# 14_RAM-DDR3_1X16BIT.net
KiCad netlist of a schematic drawn in Altium Designer
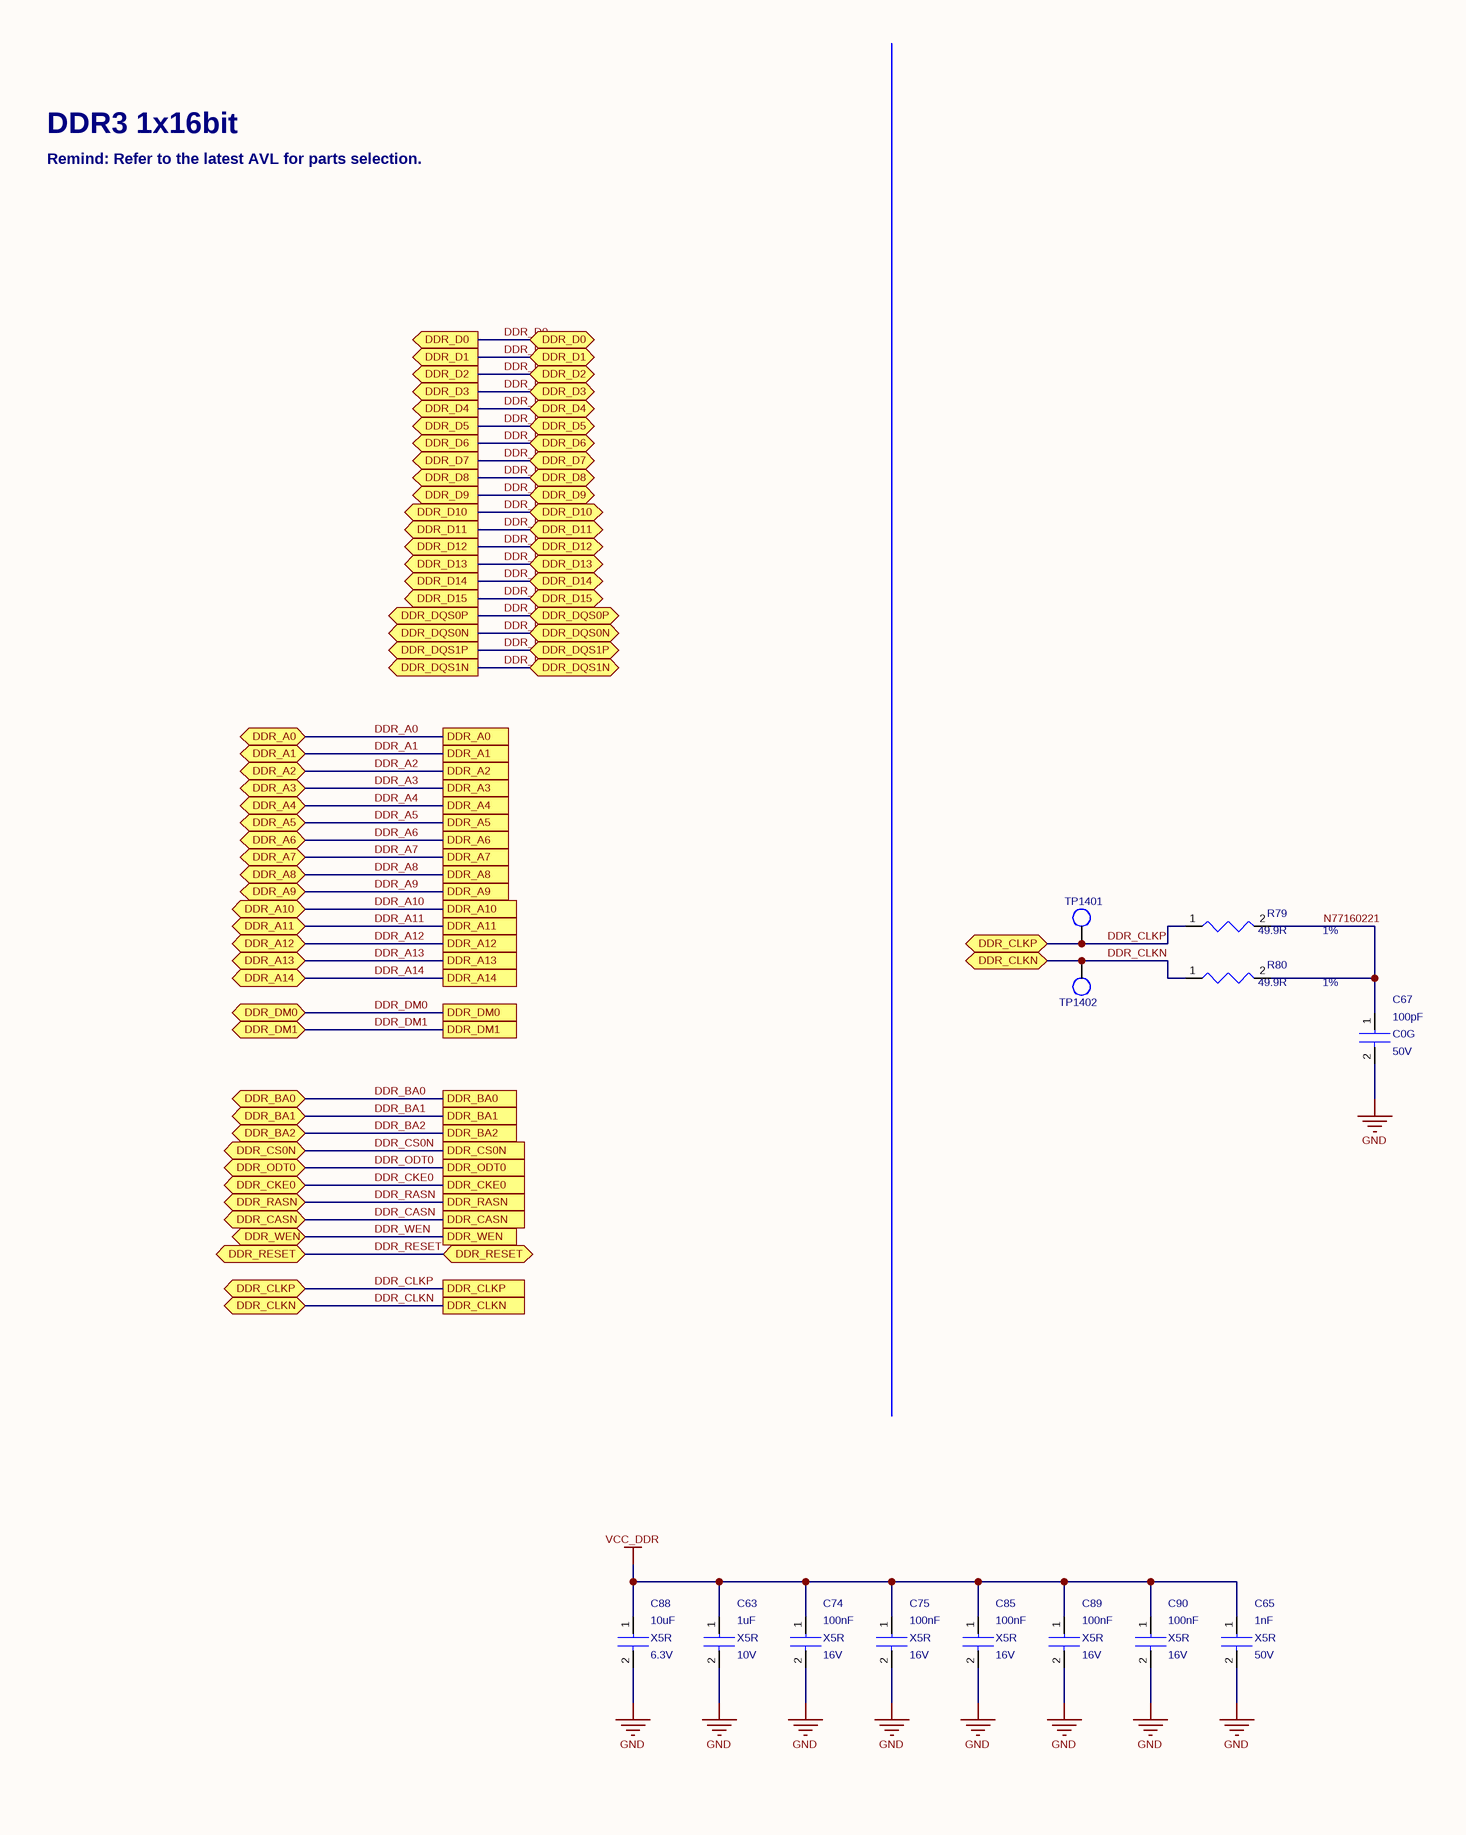
[diagram p0: 14_RAM-DDR3_1X16BIT.SchDoc, left]
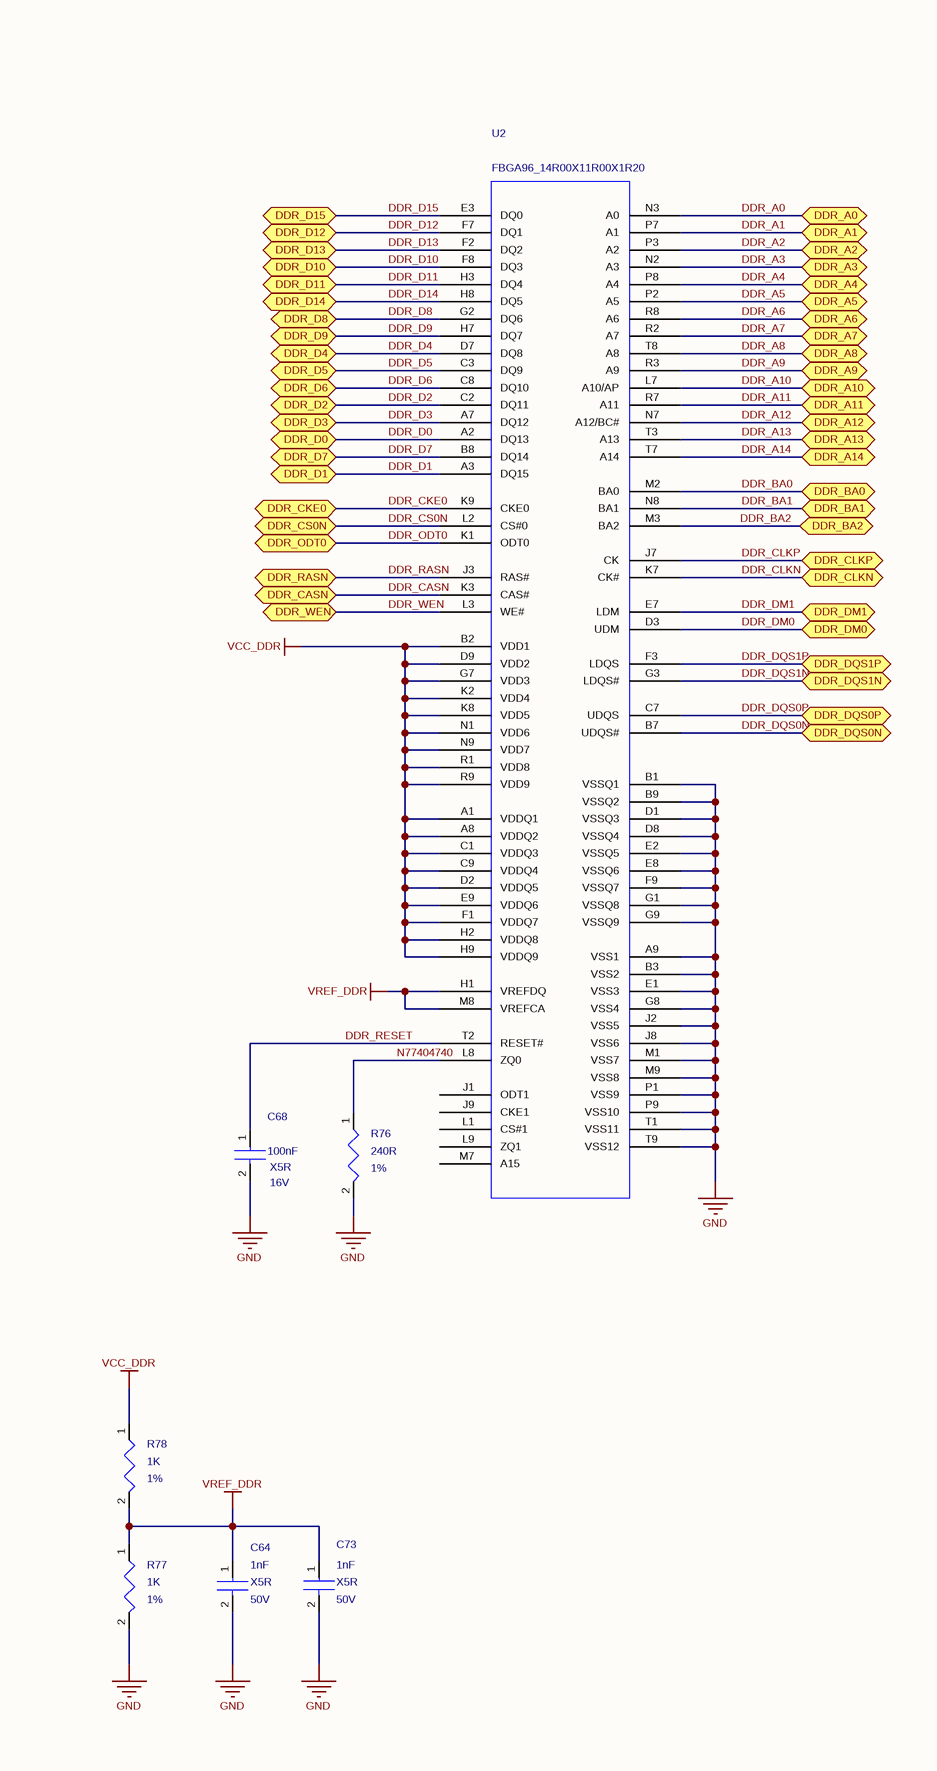
[diagram p1: 14_RAM-DDR3_1X16BIT.SchDoc, right]

(export (version "E")
  (design (tool "Eeschema 10.0.6"))
  (components
    (comp (ref "C63")
      (value "1uF")
      (footprint "C0402")
      (description "cap,1.00uF,+/-10%,10V,X5R,C0402")
      (fields
        (field (name "DIELECTRIC") "X5R")
        (field (name "VOLTAGE") "10V")
        (field (name "TOLERANCE") "10%")
        (field (name "MANUFACTURER") "TDK")
        (field (name "CREATED_BY") "JJJ")
      )
      (libsource (lib "*") (part "CAP_NP_2"))
    )
    (comp (ref "C64")
      (value "1nF")
      (footprint "C0402")
      (description "cap,1.00nF,+/-10%,50V,X5R,C0402")
      (fields
        (field (name "VOLTAGE") "50V")
        (field (name "DIELECTRIC") "X5R")
        (field (name "TOLERANCE") "10%")
        (field (name "MANUFACTURER") "TDK")
        (field (name "CREATED_BY") "JJJ")
      )
      (libsource (lib "*") (part "CAP_NP_2"))
    )
    (comp (ref "C65")
      (value "1nF")
      (footprint "C0402")
      (description "cap,1.00nF,+/-10%,50V,X5R,C0402")
      (fields
        (field (name "DIELECTRIC") "X5R")
        (field (name "VOLTAGE") "50V")
        (field (name "TOLERANCE") "10%")
        (field (name "MANUFACTURER") "TDK")
        (field (name "CREATED_BY") "JJJ")
      )
      (libsource (lib "*") (part "CAP_NP_2"))
    )
    (comp (ref "C67")
      (value "100pF")
      (footprint "C0402")
      (description "cap,100.00pF,+/-10%,50V,C0G,C0402")
      (fields
        (field (name "VOLTAGE") "50V")
        (field (name "TOLERANCE") "10%")
        (field (name "MANUFACTURER") "TDK")
        (field (name "DIELECTRIC") "C0G")
        (field (name "CREATED_BY") "JJJ")
      )
      (libsource (lib "*") (part "CAP_NP_2"))
    )
    (comp (ref "C68")
      (value "100nF")
      (footprint "C0402")
      (description "cap,100.00nF,+/-10%,16V,X5R,C0402")
      (fields
        (field (name "TOLERANCE") "10%")
        (field (name "MANUFACTURER") "TDK")
        (field (name "DIELECTRIC") "X5R")
        (field (name "VOLTAGE") "16V")
        (field (name "CREATED_BY") "JJJ")
      )
      (libsource (lib "*") (part "CAP_NP_2"))
    )
    (comp (ref "C73")
      (value "1nF")
      (footprint "C0402")
      (description "cap,1.00nF,+/-10%,50V,X5R,C0402")
      (fields
        (field (name "VOLTAGE") "50V")
        (field (name "MANUFACTURER") "TDK")
        (field (name "TOLERANCE") "10%")
        (field (name "DIELECTRIC") "X5R")
        (field (name "CREATED_BY") "JJJ")
      )
      (libsource (lib "*") (part "CAP_NP_2"))
    )
    (comp (ref "C74")
      (value "100nF")
      (footprint "C0402")
      (description "cap,100.00nF,+/-10%,16V,X5R,C0402")
      (fields
        (field (name "MANUFACTURER") "TDK")
        (field (name "TOLERANCE") "10%")
        (field (name "VOLTAGE") "16V")
        (field (name "DIELECTRIC") "X5R")
        (field (name "CREATED_BY") "JJJ")
      )
      (libsource (lib "*") (part "CAP_NP_2"))
    )
    (comp (ref "C75")
      (value "100nF")
      (footprint "C0402")
      (description "cap,100.00nF,+/-10%,16V,X5R,C0402")
      (fields
        (field (name "MANUFACTURER") "TDK")
        (field (name "TOLERANCE") "10%")
        (field (name "VOLTAGE") "16V")
        (field (name "DIELECTRIC") "X5R")
        (field (name "CREATED_BY") "JJJ")
      )
      (libsource (lib "*") (part "CAP_NP_2"))
    )
    (comp (ref "C85")
      (value "100nF")
      (footprint "C0402")
      (description "cap,100.00nF,+/-10%,16V,X5R,C0402")
      (fields
        (field (name "MANUFACTURER") "TDK")
        (field (name "TOLERANCE") "10%")
        (field (name "VOLTAGE") "16V")
        (field (name "DIELECTRIC") "X5R")
        (field (name "CREATED_BY") "JJJ")
      )
      (libsource (lib "*") (part "CAP_NP_2"))
    )
    (comp (ref "C88")
      (value "10uF")
      (footprint "C0603")
      (description "cap,10.00uF,+/-10%,6.3V,X5R,C0603")
      (fields
        (field (name "MANUFACTURER") "TDK")
        (field (name "TOLERANCE") "10%")
        (field (name "VOLTAGE") "6.3V")
        (field (name "DIELECTRIC") "X5R")
        (field (name "CREATED_BY") "JJJ")
      )
      (libsource (lib "*") (part "CAP_NP_2"))
    )
    (comp (ref "C89")
      (value "100nF")
      (footprint "C0402")
      (description "cap,100.00nF,+/-10%,16V,X5R,C0402")
      (fields
        (field (name "MANUFACTURER") "TDK")
        (field (name "TOLERANCE") "10%")
        (field (name "VOLTAGE") "16V")
        (field (name "DIELECTRIC") "X5R")
        (field (name "CREATED_BY") "JJJ")
      )
      (libsource (lib "*") (part "CAP_NP_2"))
    )
    (comp (ref "C90")
      (value "100nF")
      (footprint "C0402")
      (description "cap,100.00nF,+/-10%,16V,X5R,C0402")
      (fields
        (field (name "DIELECTRIC") "X5R")
        (field (name "VOLTAGE") "16V")
        (field (name "TOLERANCE") "10%")
        (field (name "MANUFACTURER") "TDK")
        (field (name "CREATED_BY") "JJJ")
      )
      (libsource (lib "*") (part "CAP_NP_2"))
    )
    (comp (ref "R76")
      (value "240R")
      (footprint "R0402")
      (description "?用厚膜电阻,240R,+/-1%,R0402,1/16W.")
      (fields
        (field (name "TOLERANCE") "1%")
        (field (name "MANUFACTURER") "YAGEO")
        (field (name "Comment") "RESISTOR")
        (field (name "CREATED_BY") "YTL")
      )
      (libsource (lib "*") (part "RESISTOR"))
    )
    (comp (ref "R77")
      (value "1K")
      (footprint "R0402")
      (description "?用厚膜电阻,1K,+/-1%,R0402,1/16W.")
      (fields
        (field (name "TOLERANCE") "1%")
        (field (name "MANUFACTURER") "YAGEO")
        (field (name "Comment") "RESISTOR")
        (field (name "CREATED_BY") "YTL")
      )
      (libsource (lib "*") (part "RESISTOR"))
    )
    (comp (ref "R78")
      (value "1K")
      (footprint "R0402")
      (description "?用厚膜电阻,1K,+/-1%,R0402,1/16W.")
      (fields
        (field (name "MANUFACTURER") "YAGEO")
        (field (name "TOLERANCE") "1%")
        (field (name "Comment") "RESISTOR")
        (field (name "CREATED_BY") "YTL")
      )
      (libsource (lib "*") (part "RESISTOR"))
    )
    (comp (ref "R79")
      (value "49.9R")
      (footprint "R0402")
      (description "?用厚膜电阻,49R9,+/-1%,R0402,1/16W.")
      (fields
        (field (name "TOLERANCE") "1%")
        (field (name "MANUFACTURER") "YAGEO")
        (field (name "Comment") "RESISTOR")
        (field (name "CREATED_BY") "YTL")
      )
      (libsource (lib "*") (part "RESISTOR"))
    )
    (comp (ref "R80")
      (value "49.9R")
      (footprint "R0402")
      (description "?用厚膜电阻,49R9,+/-1%,R0402,1/16W.")
      (fields
        (field (name "TOLERANCE") "1%")
        (field (name "MANUFACTURER") "YAGEO")
        (field (name "Comment") "RESISTOR")
        (field (name "CREATED_BY") "YTL")
      )
      (libsource (lib "*") (part "RESISTOR"))
    )
    (comp (ref "TP1401")
      (value "TP_0.7")
      (footprint "TEST")
      (description "Test Point 0.7mm")
      (fields (field (name "CREATED BY") "JJJ"))
      (libsource (lib "*") (part "TP"))
    )
    (comp (ref "TP1402")
      (value "TP_0.7")
      (footprint "TEST")
      (description "Test Point 0.7mm")
      (fields (field (name "CREATED BY") "JJJ"))
      (libsource (lib "*") (part "TP"))
    )
    (comp (ref "U2")
      (value "DDR3_16BIT")
      (footprint "FBGA96_14R00X11R00X1R20")
      (description "2Gb/M15T1G1664A-DEBG2CS")
      (fields
        (field (name "MANUFACTURER") "ESMT")
        (field (name "PCB DECAL") "FBGA96_14R00X11R00X1R20")
        (field (name "CREATED_BY") "JJJ")
      )
      (libsource (lib "*") (part "DDR3_16BIT"))
    )
  )
  (nets
    (net (code "1") (name "/DDR_A0") (class "Default")
      (node (ref "U2") (pin "N3") (pinfunction "A0_N3") (pintype "passive"))
    )
    (net (code "2") (name "/DDR_A1") (class "Default")
      (node (ref "U2") (pin "P7") (pinfunction "A1_P7") (pintype "passive"))
    )
    (net (code "3") (name "/DDR_A2") (class "Default")
      (node (ref "U2") (pin "P3") (pinfunction "A2_P3") (pintype "passive"))
    )
    (net (code "4") (name "/DDR_A3") (class "Default")
      (node (ref "U2") (pin "N2") (pinfunction "A3_N2") (pintype "passive"))
    )
    (net (code "5") (name "/DDR_A4") (class "Default")
      (node (ref "U2") (pin "P8") (pinfunction "A4_P8") (pintype "passive"))
    )
    (net (code "6") (name "/DDR_A5") (class "Default")
      (node (ref "U2") (pin "P2") (pinfunction "A5_P2") (pintype "passive"))
    )
    (net (code "7") (name "/DDR_A6") (class "Default")
      (node (ref "U2") (pin "R8") (pinfunction "A6_R8") (pintype "passive"))
    )
    (net (code "8") (name "/DDR_A7") (class "Default")
      (node (ref "U2") (pin "R2") (pinfunction "A7_R2") (pintype "passive"))
    )
    (net (code "9") (name "/DDR_A8") (class "Default")
      (node (ref "U2") (pin "T8") (pinfunction "A8_T8") (pintype "passive"))
    )
    (net (code "10") (name "/DDR_A9") (class "Default")
      (node (ref "U2") (pin "R3") (pinfunction "A9_R3") (pintype "passive"))
    )
    (net (code "11") (name "/DDR_A10") (class "Default")
      (node (ref "U2") (pin "L7") (pinfunction "A10/AP_L7") (pintype "passive"))
    )
    (net (code "12") (name "/DDR_A11") (class "Default")
      (node (ref "U2") (pin "R7") (pinfunction "A11_R7") (pintype "passive"))
    )
    (net (code "13") (name "/DDR_A12") (class "Default")
      (node (ref "U2") (pin "N7") (pinfunction "A12/BC#_N7") (pintype "passive"))
    )
    (net (code "14") (name "/DDR_A13") (class "Default")
      (node (ref "U2") (pin "T3") (pinfunction "A13_T3") (pintype "passive"))
    )
    (net (code "15") (name "/DDR_A14") (class "Default")
      (node (ref "U2") (pin "T7") (pinfunction "A14_T7") (pintype "passive"))
    )
    (net (code "16") (name "/DDR_BA0") (class "Default")
      (node (ref "U2") (pin "M2") (pinfunction "BA0_M2") (pintype "passive"))
    )
    (net (code "17") (name "/DDR_BA1") (class "Default")
      (node (ref "U2") (pin "N8") (pinfunction "BA1_N8") (pintype "passive"))
    )
    (net (code "18") (name "/DDR_BA2") (class "Default")
      (node (ref "U2") (pin "M3") (pinfunction "BA2_M3") (pintype "passive"))
    )
    (net (code "19") (name "/DDR_CASN") (class "Default")
      (node (ref "U2") (pin "K3") (pinfunction "CAS#_K3") (pintype "passive"))
    )
    (net (code "20") (name "/DDR_CKE0") (class "Default")
      (node (ref "U2") (pin "K9") (pinfunction "CKE0_K9") (pintype "passive"))
    )
    (net (code "21") (name "/DDR_CLKN") (class "Default")
      (node (ref "R80") (pin "1") (pinfunction "1_1") (pintype "passive"))
      (node (ref "TP1402") (pin "1") (pinfunction "1_1") (pintype "passive"))
      (node (ref "U2") (pin "K7") (pinfunction "CK#_K7") (pintype "passive"))
    )
    (net (code "22") (name "/DDR_CLKP") (class "Default")
      (node (ref "R79") (pin "1") (pinfunction "1_1") (pintype "passive"))
      (node (ref "TP1401") (pin "1") (pinfunction "1_1") (pintype "passive"))
      (node (ref "U2") (pin "J7") (pinfunction "CK_J7") (pintype "passive"))
    )
    (net (code "23") (name "/DDR_CS0N") (class "Default")
      (node (ref "U2") (pin "L2") (pinfunction "CS#0_L2") (pintype "passive"))
    )
    (net (code "24") (name "/DDR_D0") (class "Default")
      (node (ref "U2") (pin "A2") (pinfunction "DQ13_A2") (pintype "passive"))
    )
    (net (code "25") (name "/DDR_D1") (class "Default")
      (node (ref "U2") (pin "A3") (pinfunction "DQ15_A3") (pintype "passive"))
    )
    (net (code "26") (name "/DDR_D2") (class "Default")
      (node (ref "U2") (pin "C2") (pinfunction "DQ11_C2") (pintype "passive"))
    )
    (net (code "27") (name "/DDR_D3") (class "Default")
      (node (ref "U2") (pin "A7") (pinfunction "DQ12_A7") (pintype "passive"))
    )
    (net (code "28") (name "/DDR_D4") (class "Default")
      (node (ref "U2") (pin "D7") (pinfunction "DQ8_D7") (pintype "passive"))
    )
    (net (code "29") (name "/DDR_D5") (class "Default")
      (node (ref "U2") (pin "C3") (pinfunction "DQ9_C3") (pintype "passive"))
    )
    (net (code "30") (name "/DDR_D6") (class "Default")
      (node (ref "U2") (pin "C8") (pinfunction "DQ10_C8") (pintype "passive"))
    )
    (net (code "31") (name "/DDR_D7") (class "Default")
      (node (ref "U2") (pin "B8") (pinfunction "DQ14_B8") (pintype "passive"))
    )
    (net (code "32") (name "/DDR_D8") (class "Default")
      (node (ref "U2") (pin "G2") (pinfunction "DQ6_G2") (pintype "passive"))
    )
    (net (code "33") (name "/DDR_D9") (class "Default")
      (node (ref "U2") (pin "H7") (pinfunction "DQ7_H7") (pintype "passive"))
    )
    (net (code "34") (name "/DDR_D10") (class "Default")
      (node (ref "U2") (pin "F8") (pinfunction "DQ3_F8") (pintype "passive"))
    )
    (net (code "35") (name "/DDR_D11") (class "Default")
      (node (ref "U2") (pin "H3") (pinfunction "DQ4_H3") (pintype "passive"))
    )
    (net (code "36") (name "/DDR_D12") (class "Default")
      (node (ref "U2") (pin "F7") (pinfunction "DQ1_F7") (pintype "passive"))
    )
    (net (code "37") (name "/DDR_D13") (class "Default")
      (node (ref "U2") (pin "F2") (pinfunction "DQ2_F2") (pintype "passive"))
    )
    (net (code "38") (name "/DDR_D14") (class "Default")
      (node (ref "U2") (pin "H8") (pinfunction "DQ5_H8") (pintype "passive"))
    )
    (net (code "39") (name "/DDR_D15") (class "Default")
      (node (ref "U2") (pin "E3") (pinfunction "DQ0_E3") (pintype "passive"))
    )
    (net (code "40") (name "/DDR_DM0") (class "Default")
      (node (ref "U2") (pin "D3") (pinfunction "UDM_D3") (pintype "passive"))
    )
    (net (code "41") (name "/DDR_DM1") (class "Default")
      (node (ref "U2") (pin "E7") (pinfunction "LDM_E7") (pintype "passive"))
    )
    (net (code "42") (name "/DDR_DQS0N") (class "Default")
      (node (ref "U2") (pin "B7") (pinfunction "UDQS#_B7") (pintype "passive"))
    )
    (net (code "43") (name "/DDR_DQS0P") (class "Default")
      (node (ref "U2") (pin "C7") (pinfunction "UDQS_C7") (pintype "passive"))
    )
    (net (code "44") (name "/DDR_DQS1N") (class "Default")
      (node (ref "U2") (pin "G3") (pinfunction "LDQS#_G3") (pintype "passive"))
    )
    (net (code "45") (name "/DDR_DQS1P") (class "Default")
      (node (ref "U2") (pin "F3") (pinfunction "LDQS_F3") (pintype "passive"))
    )
    (net (code "46") (name "/DDR_ODT0") (class "Default")
      (node (ref "U2") (pin "K1") (pinfunction "ODT0_K1") (pintype "passive"))
    )
    (net (code "47") (name "/DDR_RASN") (class "Default")
      (node (ref "U2") (pin "J3") (pinfunction "RAS#_J3") (pintype "passive"))
    )
    (net (code "48") (name "/DDR_RESET") (class "Default")
      (node (ref "C68") (pin "1") (pinfunction "1_1") (pintype "passive"))
      (node (ref "U2") (pin "T2") (pinfunction "RESET#_T2") (pintype "passive"))
    )
    (net (code "49") (name "/DDR_WEN") (class "Default")
      (node (ref "U2") (pin "L3") (pinfunction "WE#_L3") (pintype "passive"))
    )
    (net (code "50") (name "/N77160221") (class "Default")
      (node (ref "C67") (pin "1") (pinfunction "1_1") (pintype "passive"))
      (node (ref "R79") (pin "2") (pinfunction "2_2") (pintype "passive"))
      (node (ref "R80") (pin "2") (pinfunction "2_2") (pintype "passive"))
    )
    (net (code "51") (name "/N77404740") (class "Default")
      (node (ref "R76") (pin "1") (pinfunction "1_1") (pintype "passive"))
      (node (ref "U2") (pin "L8") (pinfunction "ZQ0_L8") (pintype "passive"))
    )
    (net (code "52") (name "GND") (class "Default")
      (node (ref "C63") (pin "2") (pinfunction "2_2") (pintype "passive"))
      (node (ref "C64") (pin "2") (pinfunction "2_2") (pintype "passive"))
      (node (ref "C65") (pin "2") (pinfunction "2_2") (pintype "passive"))
      (node (ref "C67") (pin "2") (pinfunction "2_2") (pintype "passive"))
      (node (ref "C68") (pin "2") (pinfunction "2_2") (pintype "passive"))
      (node (ref "C73") (pin "2") (pinfunction "2_2") (pintype "passive"))
      (node (ref "C74") (pin "2") (pinfunction "2_2") (pintype "passive"))
      (node (ref "C75") (pin "2") (pinfunction "2_2") (pintype "passive"))
      (node (ref "C85") (pin "2") (pinfunction "2_2") (pintype "passive"))
      (node (ref "C88") (pin "2") (pinfunction "2_2") (pintype "passive"))
      (node (ref "C89") (pin "2") (pinfunction "2_2") (pintype "passive"))
      (node (ref "C90") (pin "2") (pinfunction "2_2") (pintype "passive"))
      (node (ref "R76") (pin "2") (pinfunction "2_2") (pintype "passive"))
      (node (ref "R77") (pin "2") (pinfunction "2_2") (pintype "passive"))
      (node (ref "U2") (pin "A9") (pinfunction "VSS1_A9") (pintype "passive"))
      (node (ref "U2") (pin "B1") (pinfunction "VSSQ1_B1") (pintype "passive"))
      (node (ref "U2") (pin "B3") (pinfunction "VSS2_B3") (pintype "passive"))
      (node (ref "U2") (pin "B9") (pinfunction "VSSQ2_B9") (pintype "passive"))
      (node (ref "U2") (pin "D1") (pinfunction "VSSQ3_D1") (pintype "passive"))
      (node (ref "U2") (pin "D8") (pinfunction "VSSQ4_D8") (pintype "passive"))
      (node (ref "U2") (pin "E1") (pinfunction "VSS3_E1") (pintype "passive"))
      (node (ref "U2") (pin "E2") (pinfunction "VSSQ5_E2") (pintype "passive"))
      (node (ref "U2") (pin "E8") (pinfunction "VSSQ6_E8") (pintype "passive"))
      (node (ref "U2") (pin "F9") (pinfunction "VSSQ7_F9") (pintype "passive"))
      (node (ref "U2") (pin "G1") (pinfunction "VSSQ8_G1") (pintype "passive"))
      (node (ref "U2") (pin "G8") (pinfunction "VSS4_G8") (pintype "passive"))
      (node (ref "U2") (pin "G9") (pinfunction "VSSQ9_G9") (pintype "passive"))
      (node (ref "U2") (pin "J2") (pinfunction "VSS5_J2") (pintype "passive"))
      (node (ref "U2") (pin "J8") (pinfunction "VSS6_J8") (pintype "passive"))
      (node (ref "U2") (pin "M1") (pinfunction "VSS7_M1") (pintype "passive"))
      (node (ref "U2") (pin "M9") (pinfunction "VSS8_M9") (pintype "passive"))
      (node (ref "U2") (pin "P1") (pinfunction "VSS9_P1") (pintype "passive"))
      (node (ref "U2") (pin "P9") (pinfunction "VSS10_P9") (pintype "passive"))
      (node (ref "U2") (pin "T1") (pinfunction "VSS11_T1") (pintype "passive"))
      (node (ref "U2") (pin "T9") (pinfunction "VSS12_T9") (pintype "passive"))
    )
    (net (code "53") (name "VCC_DDR") (class "Default")
      (node (ref "C63") (pin "1") (pinfunction "1_1") (pintype "passive"))
      (node (ref "C65") (pin "1") (pinfunction "1_1") (pintype "passive"))
      (node (ref "C74") (pin "1") (pinfunction "1_1") (pintype "passive"))
      (node (ref "C75") (pin "1") (pinfunction "1_1") (pintype "passive"))
      (node (ref "C85") (pin "1") (pinfunction "1_1") (pintype "passive"))
      (node (ref "C88") (pin "1") (pinfunction "1_1") (pintype "passive"))
      (node (ref "C89") (pin "1") (pinfunction "1_1") (pintype "passive"))
      (node (ref "C90") (pin "1") (pinfunction "1_1") (pintype "passive"))
      (node (ref "R78") (pin "1") (pinfunction "1_1") (pintype "passive"))
      (node (ref "U2") (pin "A1") (pinfunction "VDDQ1_A1") (pintype "passive"))
      (node (ref "U2") (pin "A8") (pinfunction "VDDQ2_A8") (pintype "passive"))
      (node (ref "U2") (pin "B2") (pinfunction "VDD1_B2") (pintype "passive"))
      (node (ref "U2") (pin "C1") (pinfunction "VDDQ3_C1") (pintype "passive"))
      (node (ref "U2") (pin "C9") (pinfunction "VDDQ4_C9") (pintype "passive"))
      (node (ref "U2") (pin "D2") (pinfunction "VDDQ5_D2") (pintype "passive"))
      (node (ref "U2") (pin "D9") (pinfunction "VDD2_D9") (pintype "passive"))
      (node (ref "U2") (pin "E9") (pinfunction "VDDQ6_E9") (pintype "passive"))
      (node (ref "U2") (pin "F1") (pinfunction "VDDQ7_F1") (pintype "passive"))
      (node (ref "U2") (pin "G7") (pinfunction "VDD3_G7") (pintype "passive"))
      (node (ref "U2") (pin "H2") (pinfunction "VDDQ8_H2") (pintype "passive"))
      (node (ref "U2") (pin "H9") (pinfunction "VDDQ9_H9") (pintype "passive"))
      (node (ref "U2") (pin "K2") (pinfunction "VDD4_K2") (pintype "passive"))
      (node (ref "U2") (pin "K8") (pinfunction "VDD5_K8") (pintype "passive"))
      (node (ref "U2") (pin "N1") (pinfunction "VDD6_N1") (pintype "passive"))
      (node (ref "U2") (pin "N9") (pinfunction "VDD7_N9") (pintype "passive"))
      (node (ref "U2") (pin "R1") (pinfunction "VDD8_R1") (pintype "passive"))
      (node (ref "U2") (pin "R9") (pinfunction "VDD9_R9") (pintype "passive"))
    )
    (net (code "54") (name "VREF_DDR") (class "Default")
      (node (ref "C64") (pin "1") (pinfunction "1_1") (pintype "passive"))
      (node (ref "C73") (pin "1") (pinfunction "1_1") (pintype "passive"))
      (node (ref "R77") (pin "1") (pinfunction "1_1") (pintype "passive"))
      (node (ref "R78") (pin "2") (pinfunction "2_2") (pintype "passive"))
      (node (ref "U2") (pin "H1") (pinfunction "VREFDQ_H1") (pintype "passive"))
      (node (ref "U2") (pin "M8") (pinfunction "VREFCA_M8") (pintype "passive"))
    )
    (net (code "55") (name "unconnected-(U2-A15-PadM7)") (class "Default")
      (node (ref "U2") (pin "M7") (pinfunction "A15_M7") (pintype "passive"))
    )
    (net (code "56") (name "unconnected-(U2-CKE1-PadJ9)") (class "Default")
      (node (ref "U2") (pin "J9") (pinfunction "CKE1_J9") (pintype "passive"))
    )
    (net (code "57") (name "unconnected-(U2-CS#1-PadL1)") (class "Default")
      (node (ref "U2") (pin "L1") (pinfunction "CS#1_L1") (pintype "passive"))
    )
    (net (code "58") (name "unconnected-(U2-ODT1-PadJ1)") (class "Default")
      (node (ref "U2") (pin "J1") (pinfunction "ODT1_J1") (pintype "passive"))
    )
    (net (code "59") (name "unconnected-(U2-ZQ1-PadL9)") (class "Default")
      (node (ref "U2") (pin "L9") (pinfunction "ZQ1_L9") (pintype "passive"))
    )
  )
)
